# LED-Test.net
KiCad netlist of a schematic drawn in EAGLE
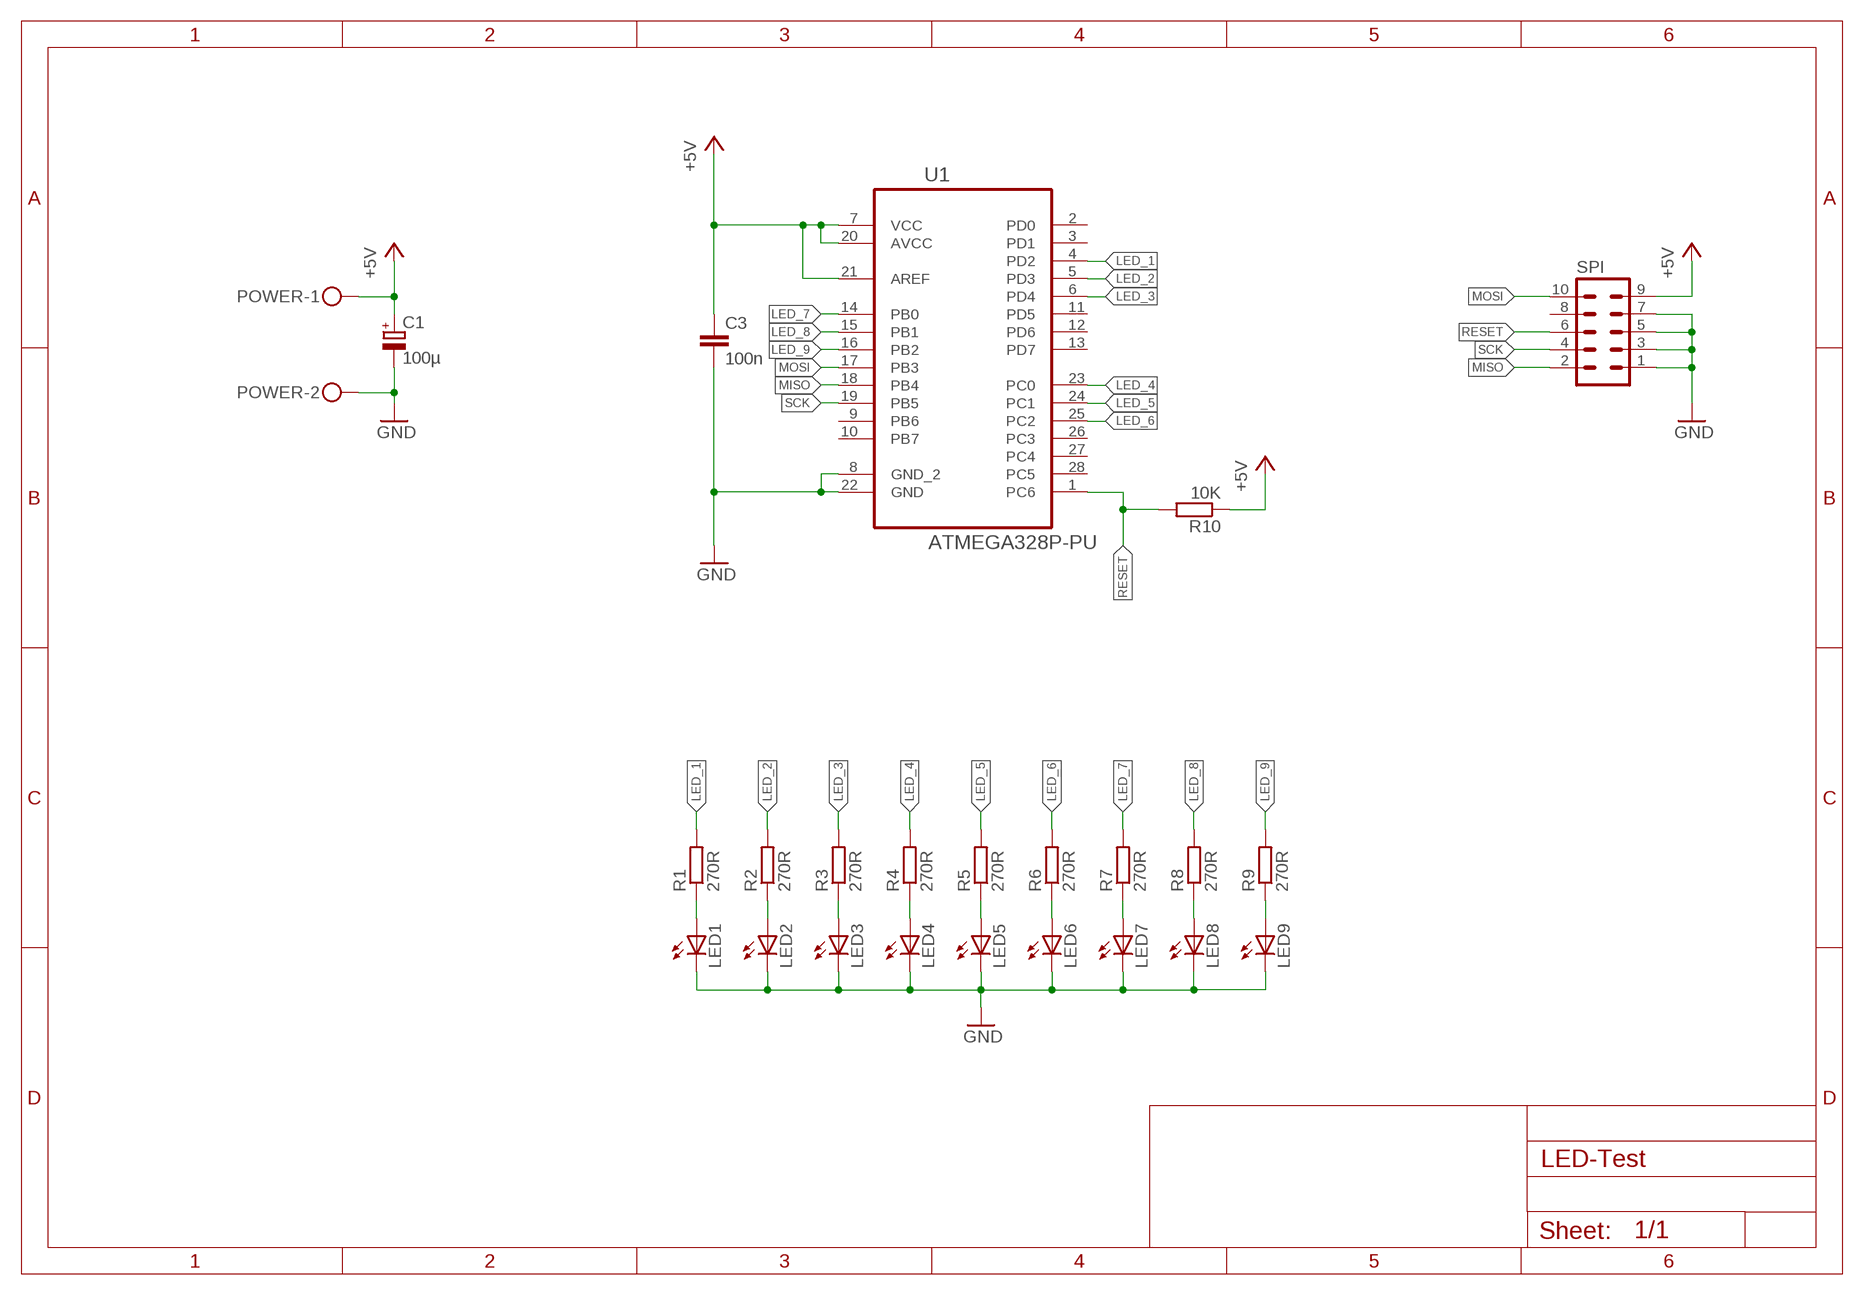
[diagram p0: schematic, sheet 1]

(export (version "E")
  (design (tool "Eeschema 10.0.6"))
  (components
    (comp (ref "C1")
      (value "100µ")
      (footprint "eagle-import:E3,5-10")
      (libsource (lib "eagle-import") (part "CPOL-EUE3.5-10"))
    )
    (comp (ref "C3")
      (value "100n")
      (footprint "eagle-import:C025-025X050")
      (libsource (lib "eagle-import") (part "C-EU025-025X050"))
    )
    (comp (ref "LED1")
      (value "LED5MM")
      (footprint "eagle-import:LED5MM")
      (libsource (lib "eagle-import") (part "LED5MM"))
    )
    (comp (ref "LED2")
      (value "LED5MM")
      (footprint "eagle-import:LED5MM")
      (libsource (lib "eagle-import") (part "LED5MM"))
    )
    (comp (ref "LED3")
      (value "LED5MM")
      (footprint "eagle-import:LED5MM")
      (libsource (lib "eagle-import") (part "LED5MM"))
    )
    (comp (ref "LED4")
      (value "LED5MM")
      (footprint "eagle-import:LED5MM")
      (libsource (lib "eagle-import") (part "LED5MM"))
    )
    (comp (ref "LED5")
      (value "LED5MM")
      (footprint "eagle-import:LED5MM")
      (libsource (lib "eagle-import") (part "LED5MM"))
    )
    (comp (ref "LED6")
      (value "LED5MM")
      (footprint "eagle-import:LED5MM")
      (libsource (lib "eagle-import") (part "LED5MM"))
    )
    (comp (ref "LED7")
      (value "LED5MM")
      (footprint "eagle-import:LED5MM")
      (libsource (lib "eagle-import") (part "LED5MM"))
    )
    (comp (ref "LED8")
      (value "LED5MM")
      (footprint "eagle-import:LED5MM")
      (libsource (lib "eagle-import") (part "LED5MM"))
    )
    (comp (ref "LED9")
      (value "LED5MM")
      (footprint "eagle-import:LED5MM")
      (libsource (lib "eagle-import") (part "LED5MM"))
    )
    (comp (ref "POWER")
      (value "W237-102")
      (footprint "eagle-import:W237-102")
      (fields (field (name "MPN") "237-102"))
      (libsource (lib "eagle-import") (part "W237-102"))
    )
    (comp (ref "R1")
      (value "270R")
      (footprint "eagle-import:0207_7")
      (libsource (lib "eagle-import") (part "R-EU_0207/7"))
    )
    (comp (ref "R2")
      (value "270R")
      (footprint "eagle-import:0207_7")
      (libsource (lib "eagle-import") (part "R-EU_0207/7"))
    )
    (comp (ref "R3")
      (value "270R")
      (footprint "eagle-import:0207_7")
      (libsource (lib "eagle-import") (part "R-EU_0207/7"))
    )
    (comp (ref "R4")
      (value "270R")
      (footprint "eagle-import:0207_7")
      (libsource (lib "eagle-import") (part "R-EU_0207/7"))
    )
    (comp (ref "R5")
      (value "270R")
      (footprint "eagle-import:0207_7")
      (libsource (lib "eagle-import") (part "R-EU_0207/7"))
    )
    (comp (ref "R6")
      (value "270R")
      (footprint "eagle-import:0207_7")
      (libsource (lib "eagle-import") (part "R-EU_0207/7"))
    )
    (comp (ref "R7")
      (value "270R")
      (footprint "eagle-import:0207_7")
      (libsource (lib "eagle-import") (part "R-EU_0207/7"))
    )
    (comp (ref "R8")
      (value "270R")
      (footprint "eagle-import:0207_7")
      (libsource (lib "eagle-import") (part "R-EU_0207/7"))
    )
    (comp (ref "R9")
      (value "270R")
      (footprint "eagle-import:0207_7")
      (libsource (lib "eagle-import") (part "R-EU_0207/7"))
    )
    (comp (ref "R10")
      (value "10K")
      (footprint "eagle-import:0207_7")
      (libsource (lib "eagle-import") (part "R-EU_0207/7"))
    )
    (comp (ref "SPI")
      (value "ML10")
      (footprint "eagle-import:ML10")
      (libsource (lib "eagle-import") (part "ML10"))
    )
    (comp (ref "U1")
      (value "ATMEGA328P-PU")
      (footprint "eagle-import:DIP254P762X457-28")
      (libsource (lib "eagle-import") (part "ATMEGA328P-PU"))
    )
  )
  (nets
    (net (code "1") (name "+5V") (class "Default")
      (node (ref "C1") (pin "+") (pinfunction "+_+") (pintype "passive"))
      (node (ref "C3") (pin "1") (pinfunction "1_1") (pintype "passive"))
      (node (ref "POWER") (pin "1") (pinfunction "KL_1") (pintype "passive"))
      (node (ref "R10") (pin "1") (pinfunction "1_1") (pintype "passive"))
      (node (ref "SPI") (pin "9") (pinfunction "9_9") (pintype "passive"))
      (node (ref "U1") (pin "20") (pinfunction "AVCC_20") (pintype "power_in"))
      (node (ref "U1") (pin "21") (pinfunction "AREF_21") (pintype "input"))
      (node (ref "U1") (pin "7") (pinfunction "VCC_7") (pintype "power_in"))
    )
    (net (code "2") (name "GND") (class "Default")
      (node (ref "C1") (pin "-") (pinfunction "-_-") (pintype "passive"))
      (node (ref "C3") (pin "2") (pinfunction "2_2") (pintype "passive"))
      (node (ref "LED1") (pin "K") (pinfunction "C_K") (pintype "passive"))
      (node (ref "LED2") (pin "K") (pinfunction "C_K") (pintype "passive"))
      (node (ref "LED3") (pin "K") (pinfunction "C_K") (pintype "passive"))
      (node (ref "LED4") (pin "K") (pinfunction "C_K") (pintype "passive"))
      (node (ref "LED5") (pin "K") (pinfunction "C_K") (pintype "passive"))
      (node (ref "LED6") (pin "K") (pinfunction "C_K") (pintype "passive"))
      (node (ref "LED7") (pin "K") (pinfunction "C_K") (pintype "passive"))
      (node (ref "LED8") (pin "K") (pinfunction "C_K") (pintype "passive"))
      (node (ref "LED9") (pin "K") (pinfunction "C_K") (pintype "passive"))
      (node (ref "POWER") (pin "2") (pinfunction "KL_2") (pintype "passive"))
      (node (ref "SPI") (pin "1") (pinfunction "1_1") (pintype "passive"))
      (node (ref "SPI") (pin "3") (pinfunction "3_3") (pintype "passive"))
      (node (ref "SPI") (pin "5") (pinfunction "5_5") (pintype "passive"))
      (node (ref "SPI") (pin "7") (pinfunction "7_7") (pintype "passive"))
      (node (ref "U1") (pin "22") (pinfunction "GND_22") (pintype "passive"))
      (node (ref "U1") (pin "8") (pinfunction "GND_2_8") (pintype "passive"))
    )
    (net (code "3") (name "LED_1") (class "Default")
      (node (ref "R1") (pin "2") (pinfunction "2_2") (pintype "passive"))
      (node (ref "U1") (pin "4") (pinfunction "PD2_4") (pintype "bidirectional"))
    )
    (net (code "4") (name "LED_2") (class "Default")
      (node (ref "R2") (pin "2") (pinfunction "2_2") (pintype "passive"))
      (node (ref "U1") (pin "5") (pinfunction "PD3_5") (pintype "bidirectional"))
    )
    (net (code "5") (name "LED_3") (class "Default")
      (node (ref "R3") (pin "2") (pinfunction "2_2") (pintype "passive"))
      (node (ref "U1") (pin "6") (pinfunction "PD4_6") (pintype "bidirectional"))
    )
    (net (code "6") (name "LED_4") (class "Default")
      (node (ref "R4") (pin "2") (pinfunction "2_2") (pintype "passive"))
      (node (ref "U1") (pin "23") (pinfunction "PC0_23") (pintype "bidirectional"))
    )
    (net (code "7") (name "LED_5") (class "Default")
      (node (ref "R5") (pin "2") (pinfunction "2_2") (pintype "passive"))
      (node (ref "U1") (pin "24") (pinfunction "PC1_24") (pintype "bidirectional"))
    )
    (net (code "8") (name "LED_6") (class "Default")
      (node (ref "R6") (pin "2") (pinfunction "2_2") (pintype "passive"))
      (node (ref "U1") (pin "25") (pinfunction "PC2_25") (pintype "bidirectional"))
    )
    (net (code "9") (name "LED_7") (class "Default")
      (node (ref "R7") (pin "2") (pinfunction "2_2") (pintype "passive"))
      (node (ref "U1") (pin "14") (pinfunction "PB0_14") (pintype "bidirectional"))
    )
    (net (code "10") (name "LED_8") (class "Default")
      (node (ref "R8") (pin "2") (pinfunction "2_2") (pintype "passive"))
      (node (ref "U1") (pin "15") (pinfunction "PB1_15") (pintype "bidirectional"))
    )
    (net (code "11") (name "LED_9") (class "Default")
      (node (ref "R9") (pin "2") (pinfunction "2_2") (pintype "passive"))
      (node (ref "U1") (pin "16") (pinfunction "PB2_16") (pintype "bidirectional"))
    )
    (net (code "12") (name "MISO") (class "Default")
      (node (ref "SPI") (pin "2") (pinfunction "2_2") (pintype "passive"))
      (node (ref "U1") (pin "18") (pinfunction "PB4_18") (pintype "bidirectional"))
    )
    (net (code "13") (name "MOSI") (class "Default")
      (node (ref "SPI") (pin "10") (pinfunction "10_10") (pintype "passive"))
      (node (ref "U1") (pin "17") (pinfunction "PB3_17") (pintype "bidirectional"))
    )
    (net (code "14") (name "Net-(LED1-PadA)") (class "Default")
      (node (ref "LED1") (pin "A") (pinfunction "A_A") (pintype "passive"))
      (node (ref "R1") (pin "1") (pinfunction "1_1") (pintype "passive"))
    )
    (net (code "15") (name "Net-(LED2-PadA)") (class "Default")
      (node (ref "LED2") (pin "A") (pinfunction "A_A") (pintype "passive"))
      (node (ref "R2") (pin "1") (pinfunction "1_1") (pintype "passive"))
    )
    (net (code "16") (name "Net-(LED3-PadA)") (class "Default")
      (node (ref "LED3") (pin "A") (pinfunction "A_A") (pintype "passive"))
      (node (ref "R3") (pin "1") (pinfunction "1_1") (pintype "passive"))
    )
    (net (code "17") (name "Net-(LED4-PadA)") (class "Default")
      (node (ref "LED4") (pin "A") (pinfunction "A_A") (pintype "passive"))
      (node (ref "R4") (pin "1") (pinfunction "1_1") (pintype "passive"))
    )
    (net (code "18") (name "Net-(LED5-PadA)") (class "Default")
      (node (ref "LED5") (pin "A") (pinfunction "A_A") (pintype "passive"))
      (node (ref "R5") (pin "1") (pinfunction "1_1") (pintype "passive"))
    )
    (net (code "19") (name "Net-(LED6-PadA)") (class "Default")
      (node (ref "LED6") (pin "A") (pinfunction "A_A") (pintype "passive"))
      (node (ref "R6") (pin "1") (pinfunction "1_1") (pintype "passive"))
    )
    (net (code "20") (name "Net-(LED7-PadA)") (class "Default")
      (node (ref "LED7") (pin "A") (pinfunction "A_A") (pintype "passive"))
      (node (ref "R7") (pin "1") (pinfunction "1_1") (pintype "passive"))
    )
    (net (code "21") (name "Net-(LED8-PadA)") (class "Default")
      (node (ref "LED8") (pin "A") (pinfunction "A_A") (pintype "passive"))
      (node (ref "R8") (pin "1") (pinfunction "1_1") (pintype "passive"))
    )
    (net (code "22") (name "Net-(LED9-PadA)") (class "Default")
      (node (ref "LED9") (pin "A") (pinfunction "A_A") (pintype "passive"))
      (node (ref "R9") (pin "1") (pinfunction "1_1") (pintype "passive"))
    )
    (net (code "23") (name "RESET") (class "Default")
      (node (ref "R10") (pin "2") (pinfunction "2_2") (pintype "passive"))
      (node (ref "SPI") (pin "6") (pinfunction "6_6") (pintype "passive"))
      (node (ref "U1") (pin "1") (pinfunction "PC6_1") (pintype "bidirectional"))
    )
    (net (code "24") (name "SCK") (class "Default")
      (node (ref "SPI") (pin "4") (pinfunction "4_4") (pintype "passive"))
      (node (ref "U1") (pin "19") (pinfunction "PB5_19") (pintype "bidirectional"))
    )
    (net (code "25") (name "unconnected-(SPI-Pad8)") (class "Default")
      (node (ref "SPI") (pin "8") (pinfunction "8_8") (pintype "passive"))
    )
    (net (code "26") (name "unconnected-(U1-PB6-Pad9)") (class "Default")
      (node (ref "U1") (pin "9") (pinfunction "PB6_9") (pintype "bidirectional"))
    )
    (net (code "27") (name "unconnected-(U1-PB7-Pad10)") (class "Default")
      (node (ref "U1") (pin "10") (pinfunction "PB7_10") (pintype "bidirectional"))
    )
    (net (code "28") (name "unconnected-(U1-PC3-Pad26)") (class "Default")
      (node (ref "U1") (pin "26") (pinfunction "PC3_26") (pintype "bidirectional"))
    )
    (net (code "29") (name "unconnected-(U1-PC4-Pad27)") (class "Default")
      (node (ref "U1") (pin "27") (pinfunction "PC4_27") (pintype "bidirectional"))
    )
    (net (code "30") (name "unconnected-(U1-PC5-Pad28)") (class "Default")
      (node (ref "U1") (pin "28") (pinfunction "PC5_28") (pintype "bidirectional"))
    )
    (net (code "31") (name "unconnected-(U1-PD0-Pad2)") (class "Default")
      (node (ref "U1") (pin "2") (pinfunction "PD0_2") (pintype "bidirectional"))
    )
    (net (code "32") (name "unconnected-(U1-PD1-Pad3)") (class "Default")
      (node (ref "U1") (pin "3") (pinfunction "PD1_3") (pintype "bidirectional"))
    )
    (net (code "33") (name "unconnected-(U1-PD5-Pad11)") (class "Default")
      (node (ref "U1") (pin "11") (pinfunction "PD5_11") (pintype "bidirectional"))
    )
    (net (code "34") (name "unconnected-(U1-PD6-Pad12)") (class "Default")
      (node (ref "U1") (pin "12") (pinfunction "PD6_12") (pintype "bidirectional"))
    )
    (net (code "35") (name "unconnected-(U1-PD7-Pad13)") (class "Default")
      (node (ref "U1") (pin "13") (pinfunction "PD7_13") (pintype "bidirectional"))
    )
  )
)
